# ACCEL_LIS2DH.net
KiCad netlist of a schematic drawn in Altium Designer
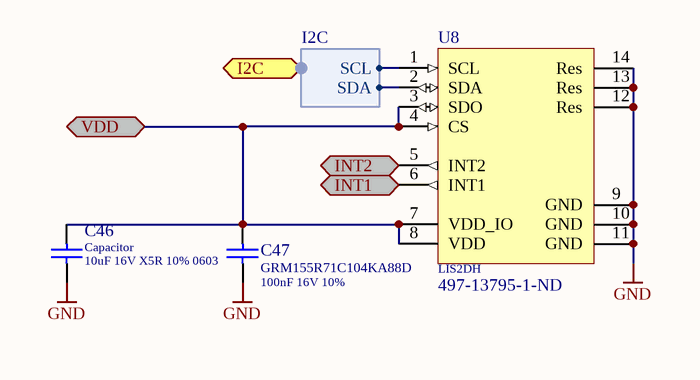
[diagram p0: ACCEL_LIS2DH.SchDoc]

(export (version "E")
  (design (tool "Eeschema 10.0.6"))
  (components
    (comp (ref "C46")
      (value "Capacitor")
      (footprint "CAP_SMD:0603")
      (description "Ceramic capacitor")
      (fields
        (field (name "VOLTAGE") "16V")
        (field (name "TOLERANCE") "10%")
        (field (name "ALTIUM_VALUE") "10uF 16V X5R 10% ")
      )
      (libsource (lib "Passive") (part "Capacitor ceramic"))
    )
    (comp (ref "C47")
      (value "GRM155R71C104KA88D")
      (footprint "CAP_SMD:0402")
      (description "Ceramic capacitor")
      (fields
        (field (name "VOLTAGE") "16V")
        (field (name "TOLERANCE") "10%")
        (field (name "ALTIUM_VALUE") "100nF 16V 10%")
      )
      (libsource (lib "") (part "Capacitor ceramic_1"))
    )
    (comp (ref "U8")
      (value "LIS2DH")
      (footprint "QFN_DFN:LGA-14-2x2")
      (description "MEMS digital output motion sensor: ultra low-power high performance 3-axis “femto” accelerometer")
      (fields (field (name "SUPPLIER PART NUMBER 1") "497-13795-1-ND"))
      (libsource (lib "IC_MEMS") (part "LIS2DH"))
    )
  )
  (nets
    (net (code "2") (name "/INT1") (class "Default")
      (node (ref "U8") (pin "6") (pinfunction "INT1_6") (pintype "output"))
    )
    (net (code "3") (name "/INT2") (class "Default")
      (node (ref "U8") (pin "5") (pinfunction "INT2_5") (pintype "output"))
    )
    (net (code "4") (name "/SCL") (class "Default")
      (node (ref "U8") (pin "1") (pinfunction "SCL_1") (pintype "input"))
    )
    (net (code "5") (name "/SDA") (class "Default")
      (node (ref "U8") (pin "2") (pinfunction "SDA_2") (pintype "bidirectional"))
    )
    (net (code "6") (name "/VDD") (class "Default")
      (node (ref "C46") (pin "2") (pinfunction "2_2") (pintype "passive"))
      (node (ref "C47") (pin "1") (pinfunction "1_1") (pintype "passive"))
      (node (ref "U8") (pin "3") (pinfunction "SDO_3") (pintype "bidirectional"))
      (node (ref "U8") (pin "4") (pinfunction "CS_4") (pintype "input"))
      (node (ref "U8") (pin "7") (pinfunction "VDD_IO_7") (pintype "passive"))
      (node (ref "U8") (pin "8") (pinfunction "VDD_8") (pintype "passive"))
    )
    (net (code "8") (name "GND") (class "Default")
      (node (ref "C46") (pin "1") (pinfunction "1_1") (pintype "passive"))
      (node (ref "C47") (pin "2") (pinfunction "2_2") (pintype "passive"))
      (node (ref "U8") (pin "10") (pinfunction "GND_10") (pintype "passive"))
      (node (ref "U8") (pin "11") (pinfunction "GND_11") (pintype "passive"))
      (node (ref "U8") (pin "12") (pinfunction "Res_12") (pintype "passive"))
      (node (ref "U8") (pin "13") (pinfunction "Res_13") (pintype "passive"))
      (node (ref "U8") (pin "14") (pinfunction "Res_14") (pintype "passive"))
      (node (ref "U8") (pin "9") (pinfunction "GND_9") (pintype "passive"))
    )
  )
)
